# OZ440-SE100-CAR003_sheet4.net
KiCad netlist of a schematic drawn in Altium Designer
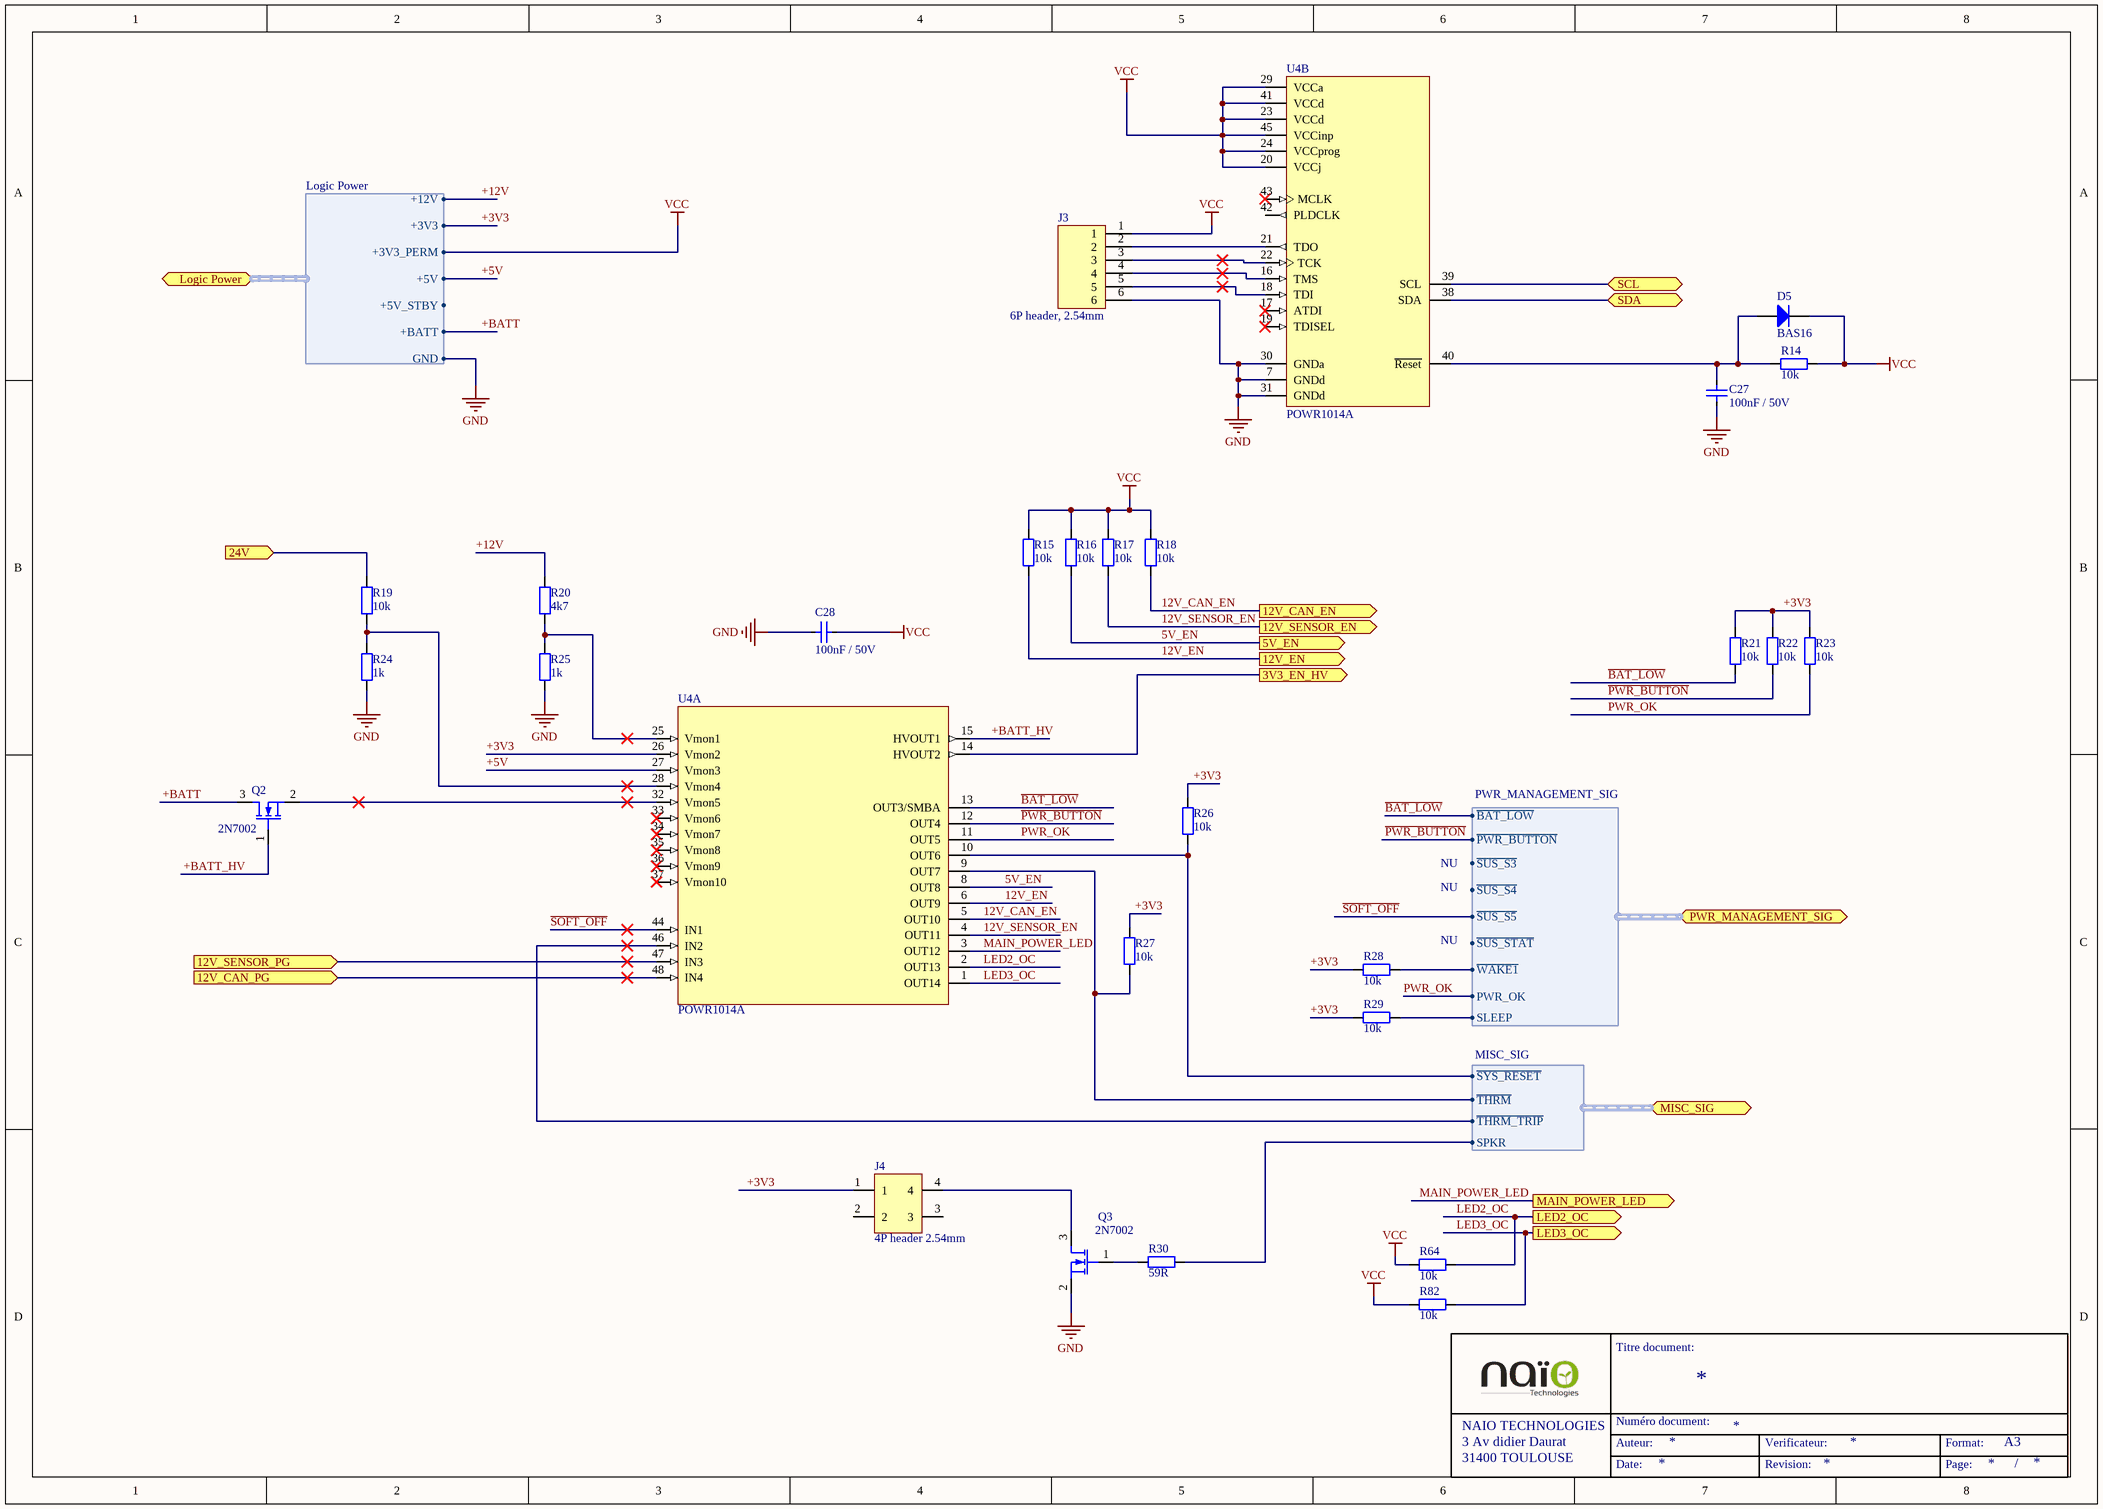
[diagram p0: OZ440-SE100-CAR003_sheet4.SchDoc]

(export (version "E")
  (design (tool "Eeschema 10.0.6"))
  (components
    (comp (ref "C27")
      (value "CAP-SMD")
      (footprint "C0805-STD")
      (description "0805 100nF / 50V  X7R ceramic capacitor")
      (fields
        (field (name "DISPLAYED REFERENCE") "100nF / 50V")
        (field (name "TOLERANCE") "+/- 10%")
        (field (name "MANUFACTURER") "vishay")
      )
      (libsource (lib "lib_NAIO") (part "CAP-SMD"))
    )
    (comp (ref "C28")
      (value "CAP-SMD")
      (footprint "C0805-STD")
      (description "0805 100nF / 50V  X7R ceramic capacitor")
      (fields
        (field (name "DISPLAYED REFERENCE") "100nF / 50V")
        (field (name "TOLERANCE") "+/- 10%")
        (field (name "MANUFACTURER") "vishay")
      )
      (libsource (lib "lib_NAIO") (part "CAP-SMD"))
    )
    (comp (ref "D5")
      (value "BAS16-SOT23")
      (footprint "SOT23-STD")
      (description "100V / 120mA signal  diode")
      (fields (field (name "DISPLAYED REFERENCE") "BAS16") (field (name "MANUFACTURER") "NXP"))
      (libsource (lib "lib_NAIO") (part "BAS16-SOT23"))
    )
    (comp (ref "J3")
      (value "CONN-STD-6P_1ROW")
      (footprint "6P_HEADER-STD_TH_1ROW")
      (description "6P, 1 row, 2.54mm header")
      (fields (field (name "DISPLAYED REFERENCE") "6P header, 2.54mm") (field (name "MANUFACTURER") "FCI"))
      (libsource (lib "lib_NAIO") (part "CONN-STD-6P_1ROW"))
    )
    (comp (ref "J4")
      (value "CONN-STD-4P_2ROW")
      (footprint "4P_HEADER-SPE-1241050-2")
      (description "4P, 2 rows, 2.54mm header")
      (fields
        (field (name "DISPLAYED REFERENCE") "4P header 2.54mm")
        (field (name "MANUFACTURER") "TE CONNECTIVITY")
      )
      (libsource (lib "lib_NAIO") (part "CONN-STD-4P_2ROW"))
    )
    (comp (ref "Q2")
      (value "2N7002-SMD3P")
      (footprint "SOT23-SPE-2N7002")
      (description "N-Channel Enhancement Mode Field Effect Transistor")
      (fields (field (name "DISPLAYED REFERENCE") "2N7002") (field (name "MANUFACTURER") "FAIRCHILD"))
      (libsource (lib "lib_NAIO") (part "2N7002-SMD3P"))
    )
    (comp (ref "Q3")
      (value "2N7002-SMD3P")
      (footprint "SOT23-SPE-2N7002")
      (description "N-Channel Enhancement Mode Field Effect Transistor")
      (fields (field (name "DISPLAYED REFERENCE") "2N7002") (field (name "MANUFACTURER") "FAIRCHILD"))
      (libsource (lib "lib_NAIO") (part "2N7002-SMD3P"))
    )
    (comp (ref "R14")
      (value "RES-SMD")
      (footprint "R0805-STD")
      (description "10k Ohm 0805 SMD resistor")
      (fields
        (field (name "DISPLAYED REFERENCE") "10k")
        (field (name "TOLERANCE") "1 %")
        (field (name "MANUFACTURER") "Vishay")
      )
      (libsource (lib "") (part "RES-SMD_2"))
    )
    (comp (ref "R15")
      (value "RES-SMD")
      (footprint "R0805-STD")
      (description "10k Ohm 0805 SMD resistor")
      (fields
        (field (name "DISPLAYED REFERENCE") "10k")
        (field (name "TOLERANCE") "1 %")
        (field (name "MANUFACTURER") "Vishay")
      )
      (libsource (lib "") (part "RES-SMD_1"))
    )
    (comp (ref "R16")
      (value "RES-SMD")
      (footprint "R0805-STD")
      (description "10k Ohm 0805 SMD resistor")
      (fields
        (field (name "DISPLAYED REFERENCE") "10k")
        (field (name "TOLERANCE") "1 %")
        (field (name "MANUFACTURER") "Vishay")
      )
      (libsource (lib "") (part "RES-SMD_1"))
    )
    (comp (ref "R17")
      (value "RES-SMD")
      (footprint "R0805-STD")
      (description "10k Ohm 0805 SMD resistor")
      (fields
        (field (name "DISPLAYED REFERENCE") "10k")
        (field (name "TOLERANCE") "1 %")
        (field (name "MANUFACTURER") "Vishay")
      )
      (libsource (lib "") (part "RES-SMD_1"))
    )
    (comp (ref "R18")
      (value "RES-SMD")
      (footprint "R0805-STD")
      (description "10k Ohm 0805 SMD resistor")
      (fields
        (field (name "DISPLAYED REFERENCE") "10k")
        (field (name "TOLERANCE") "1 %")
        (field (name "MANUFACTURER") "Vishay")
      )
      (libsource (lib "") (part "RES-SMD_1"))
    )
    (comp (ref "R19")
      (value "RES-SMD")
      (footprint "R0805-STD")
      (description "10k Ohm 0805 SMD resistor")
      (fields
        (field (name "DISPLAYED REFERENCE") "10k")
        (field (name "TOLERANCE") "1 %")
        (field (name "MANUFACTURER") "Vishay")
      )
      (libsource (lib "lib_NAIO") (part "RES-SMD"))
    )
    (comp (ref "R20")
      (value "RES-SMD")
      (footprint "R0805-STD")
      (description "4,7k Ohm 0805 SMD resistor")
      (fields
        (field (name "DISPLAYED REFERENCE") "4k7")
        (field (name "TOLERANCE") "1 %")
        (field (name "MANUFACTURER") "Vishay")
      )
      (libsource (lib "lib_NAIO") (part "RES-SMD"))
    )
    (comp (ref "R21")
      (value "RES-SMD")
      (footprint "R0805-STD")
      (description "10k Ohm 0805 SMD resistor")
      (fields
        (field (name "DISPLAYED REFERENCE") "10k")
        (field (name "TOLERANCE") "1 %")
        (field (name "MANUFACTURER") "Vishay")
      )
      (libsource (lib "") (part "RES-SMD_1"))
    )
    (comp (ref "R22")
      (value "RES-SMD")
      (footprint "R0805-STD")
      (description "10k Ohm 0805 SMD resistor")
      (fields
        (field (name "DISPLAYED REFERENCE") "10k")
        (field (name "TOLERANCE") "1 %")
        (field (name "MANUFACTURER") "Vishay")
      )
      (libsource (lib "") (part "RES-SMD_1"))
    )
    (comp (ref "R23")
      (value "RES-SMD")
      (footprint "R0805-STD")
      (description "10k Ohm 0805 SMD resistor")
      (fields
        (field (name "DISPLAYED REFERENCE") "10k")
        (field (name "TOLERANCE") "1 %")
        (field (name "MANUFACTURER") "Vishay")
      )
      (libsource (lib "") (part "RES-SMD_1"))
    )
    (comp (ref "R24")
      (value "RES-SMD")
      (footprint "R0805-STD")
      (description "1k Ohm 0805 SMD resistor")
      (fields
        (field (name "DISPLAYED REFERENCE") "1k")
        (field (name "TOLERANCE") "1 %")
        (field (name "MANUFACTURER") "Vishay")
      )
      (libsource (lib "lib_NAIO") (part "RES-SMD"))
    )
    (comp (ref "R25")
      (value "RES-SMD")
      (footprint "R0805-STD")
      (description "1k Ohm 0805 SMD resistor")
      (fields
        (field (name "DISPLAYED REFERENCE") "1k")
        (field (name "TOLERANCE") "1 %")
        (field (name "MANUFACTURER") "Vishay")
      )
      (libsource (lib "lib_NAIO") (part "RES-SMD"))
    )
    (comp (ref "R26")
      (value "RES-SMD")
      (footprint "R0805-STD")
      (description "10k Ohm 0805 SMD resistor")
      (fields
        (field (name "DISPLAYED REFERENCE") "10k")
        (field (name "TOLERANCE") "1 %")
        (field (name "MANUFACTURER") "Vishay")
      )
      (libsource (lib "") (part "RES-SMD_1"))
    )
    (comp (ref "R27")
      (value "RES-SMD")
      (footprint "R0805-STD")
      (description "10k Ohm 0805 SMD resistor")
      (fields
        (field (name "DISPLAYED REFERENCE") "10k")
        (field (name "TOLERANCE") "1 %")
        (field (name "MANUFACTURER") "Vishay")
      )
      (libsource (lib "") (part "RES-SMD_1"))
    )
    (comp (ref "R28")
      (value "RES-SMD")
      (footprint "R0805-STD")
      (description "10k Ohm 0805 SMD resistor")
      (fields
        (field (name "DISPLAYED REFERENCE") "10k")
        (field (name "TOLERANCE") "1 %")
        (field (name "MANUFACTURER") "Vishay")
      )
      (libsource (lib "") (part "RES-SMD_2"))
    )
    (comp (ref "R29")
      (value "RES-SMD")
      (footprint "R0805-STD")
      (description "10k Ohm 0805 SMD resistor")
      (fields
        (field (name "DISPLAYED REFERENCE") "10k")
        (field (name "TOLERANCE") "1 %")
        (field (name "MANUFACTURER") "Vishay")
      )
      (libsource (lib "") (part "RES-SMD_2"))
    )
    (comp (ref "R30")
      (value "RES-SMD")
      (footprint "R0805-STD")
      (description "59 Ohm 0805 SMD resistor")
      (fields
        (field (name "DISPLAYED REFERENCE") "59R")
        (field (name "TOLERANCE") "1 %")
        (field (name "MANUFACTURER") "Vishay")
      )
      (libsource (lib "") (part "RES-SMD_3"))
    )
    (comp (ref "R64")
      (value "RES-SMD")
      (footprint "R0805-STD")
      (description "10k Ohm 0805 SMD resistor")
      (fields
        (field (name "DISPLAYED REFERENCE") "10k")
        (field (name "TOLERANCE") "1 %")
        (field (name "MANUFACTURER") "Vishay")
      )
      (libsource (lib "") (part "RES-SMD_2"))
    )
    (comp (ref "R82")
      (value "RES-SMD")
      (footprint "R0805-STD")
      (description "10k Ohm 0805 SMD resistor")
      (fields
        (field (name "DISPLAYED REFERENCE") "10k")
        (field (name "TOLERANCE") "1 %")
        (field (name "MANUFACTURER") "Vishay")
      )
      (libsource (lib "") (part "RES-SMD_2"))
    )
    (comp (ref "U4")
      (value "PWR1014A-TQFP48")
      (footprint "TQFP48-SPE-PWR1014")
      (description "ispPAC power manager")
      (fields (field (name "DISPLAYED REFERENCE") "POWR1014A") (field (name "MANUFACTURER") "LATTICE"))
      (libsource (lib "lib_NAIO") (part "PWR1014A-TQFP48"))
    )
  )
  (nets
    (net (code "5") (name "/+3V3") (class "Default")
      (node (ref "J4") (pin "1") (pinfunction "1_1") (pintype "passive"))
      (node (ref "R21") (pin "1") (pinfunction "1_1") (pintype "passive"))
      (node (ref "R22") (pin "1") (pinfunction "1_1") (pintype "passive"))
      (node (ref "R23") (pin "1") (pinfunction "1_1") (pintype "passive"))
      (node (ref "R26") (pin "1") (pinfunction "1_1") (pintype "passive"))
      (node (ref "R27") (pin "1") (pinfunction "1_1") (pintype "passive"))
      (node (ref "R28") (pin "2") (pinfunction "2_2") (pintype "passive"))
      (node (ref "R29") (pin "2") (pinfunction "2_2") (pintype "passive"))
      (node (ref "U4") (pin "26") (pinfunction "Vmon2_26") (pintype "input"))
    )
    (net (code "6") (name "/+5V") (class "Default")
      (node (ref "U4") (pin "27") (pinfunction "Vmon3_27") (pintype "input"))
    )
    (net (code "7") (name "/+12V") (class "Default")
      (node (ref "R20") (pin "2") (pinfunction "2_2") (pintype "passive"))
    )
    (net (code "8") (name "/+BATT") (class "Default")
      (node (ref "Q2") (pin "3") (pinfunction "D_3") (pintype "passive"))
    )
    (net (code "9") (name "/+BATT_HV") (class "Default")
      (node (ref "Q2") (pin "1") (pinfunction "G_1") (pintype "passive"))
      (node (ref "U4") (pin "15") (pinfunction "HVOUT1_15") (pintype "output"))
    )
    (net (code "10") (name "/3V3_EN_HV") (class "Default")
      (node (ref "U4") (pin "14") (pinfunction "HVOUT2_14") (pintype "output"))
    )
    (net (code "11") (name "/5V_EN") (class "Default")
      (node (ref "R16") (pin "2") (pinfunction "2_2") (pintype "passive"))
      (node (ref "U4") (pin "8") (pinfunction "OUT8_8") (pintype "open_collector"))
    )
    (net (code "12") (name "/12V_CAN_EN") (class "Default")
      (node (ref "R18") (pin "2") (pinfunction "2_2") (pintype "passive"))
      (node (ref "U4") (pin "5") (pinfunction "OUT10_5") (pintype "open_collector"))
    )
    (net (code "13") (name "/12V_CAN_PG") (class "Default")
      (node (ref "U4") (pin "48") (pinfunction "IN4_48") (pintype "input"))
    )
    (net (code "14") (name "/12V_EN") (class "Default")
      (node (ref "R15") (pin "2") (pinfunction "2_2") (pintype "passive"))
      (node (ref "U4") (pin "6") (pinfunction "OUT9_6") (pintype "open_collector"))
    )
    (net (code "15") (name "/12V_SENSOR_EN") (class "Default")
      (node (ref "R17") (pin "2") (pinfunction "2_2") (pintype "passive"))
      (node (ref "U4") (pin "4") (pinfunction "OUT11_4") (pintype "open_collector"))
    )
    (net (code "16") (name "/12V_SENSOR_PG") (class "Default")
      (node (ref "U4") (pin "47") (pinfunction "IN3_47") (pintype "input"))
    )
    (net (code "17") (name "/24V") (class "Default")
      (node (ref "R19") (pin "2") (pinfunction "2_2") (pintype "passive"))
    )
    (net (code "18") (name "/BAT_LOW") (class "Default")
      (node (ref "R21") (pin "2") (pinfunction "2_2") (pintype "passive"))
      (node (ref "U4") (pin "13") (pinfunction "OUT3/SMBA_13") (pintype "open_collector"))
    )
    (net (code "19") (name "/LED2_OC") (class "Default")
      (node (ref "R64") (pin "1") (pinfunction "1_1") (pintype "passive"))
      (node (ref "U4") (pin "2") (pinfunction "OUT13_2") (pintype "open_collector"))
    )
    (net (code "20") (name "/LED3_OC") (class "Default")
      (node (ref "R82") (pin "1") (pinfunction "1_1") (pintype "passive"))
      (node (ref "U4") (pin "1") (pinfunction "OUT14_1") (pintype "open_collector"))
    )
    (net (code "21") (name "/MAIN_POWER_LED") (class "Default")
      (node (ref "U4") (pin "3") (pinfunction "OUT12_3") (pintype "open_collector"))
    )
    (net (code "22") (name "/PWR_BUTTON") (class "Default")
      (node (ref "R22") (pin "2") (pinfunction "2_2") (pintype "passive"))
      (node (ref "U4") (pin "12") (pinfunction "OUT4_12") (pintype "open_collector"))
    )
    (net (code "23") (name "/PWR_OK") (class "Default")
      (node (ref "R23") (pin "2") (pinfunction "2_2") (pintype "passive"))
      (node (ref "U4") (pin "11") (pinfunction "OUT5_11") (pintype "open_collector"))
    )
    (net (code "24") (name "/SCL") (class "Default")
      (node (ref "U4") (pin "39") (pinfunction "SCL_39") (pintype "passive"))
    )
    (net (code "25") (name "/SDA") (class "Default")
      (node (ref "U4") (pin "38") (pinfunction "SDA_38") (pintype "passive"))
    )
    (net (code "26") (name "/SLEEP") (class "Default")
      (node (ref "R29") (pin "1") (pinfunction "1_1") (pintype "passive"))
    )
    (net (code "27") (name "/SOFT_OFF") (class "Default")
      (node (ref "U4") (pin "44") (pinfunction "IN1_44") (pintype "input"))
    )
    (net (code "28") (name "/SPKR") (class "Default")
      (node (ref "R30") (pin "2") (pinfunction "2_2") (pintype "passive"))
    )
    (net (code "32") (name "/~{SYS_RESET}") (class "Default")
      (node (ref "R26") (pin "2") (pinfunction "2_2") (pintype "passive"))
      (node (ref "U4") (pin "10") (pinfunction "OUT6_10") (pintype "open_collector"))
    )
    (net (code "33") (name "/~{THRM_TRIP}") (class "Default")
      (node (ref "U4") (pin "46") (pinfunction "IN2_46") (pintype "input"))
    )
    (net (code "34") (name "/~{THRM}") (class "Default")
      (node (ref "R27") (pin "2") (pinfunction "2_2") (pintype "passive"))
      (node (ref "U4") (pin "9") (pinfunction "OUT7_9") (pintype "open_collector"))
    )
    (net (code "35") (name "/~{WAKE1}") (class "Default")
      (node (ref "R28") (pin "1") (pinfunction "1_1") (pintype "passive"))
    )
    (net (code "36") (name "GND") (class "Default")
      (node (ref "C27") (pin "1") (pinfunction "1_1") (pintype "passive"))
      (node (ref "C28") (pin "1") (pinfunction "1_1") (pintype "passive"))
      (node (ref "J3") (pin "6") (pinfunction "6_6") (pintype "passive"))
      (node (ref "Q3") (pin "2") (pinfunction "S_2") (pintype "passive"))
      (node (ref "R24") (pin "1") (pinfunction "1_1") (pintype "passive"))
      (node (ref "R25") (pin "1") (pinfunction "1_1") (pintype "passive"))
      (node (ref "U4") (pin "30") (pinfunction "GNDa_30") (pintype "power_in"))
      (node (ref "U4") (pin "31") (pinfunction "GNDd_31") (pintype "power_in"))
      (node (ref "U4") (pin "7") (pinfunction "GNDd_7") (pintype "power_in"))
    )
    (net (code "37") (name "Net-(D5-A)") (class "Default")
      (node (ref "C27") (pin "2") (pinfunction "2_2") (pintype "passive"))
      (node (ref "D5") (pin "1") (pinfunction "A_1") (pintype "passive"))
      (node (ref "R14") (pin "2") (pinfunction "2_2") (pintype "passive"))
      (node (ref "U4") (pin "40") (pinfunction "Reset_40") (pintype "passive"))
    )
    (net (code "38") (name "Net-(Q2-S)") (class "Default")
      (node (ref "Q2") (pin "2") (pinfunction "S_2") (pintype "passive"))
      (node (ref "U4") (pin "32") (pinfunction "Vmon5_32") (pintype "input"))
    )
    (net (code "39") (name "Net-(Q3-D)") (class "Default")
      (node (ref "J4") (pin "4") (pinfunction "4_4") (pintype "passive"))
      (node (ref "Q3") (pin "3") (pinfunction "D_3") (pintype "passive"))
    )
    (net (code "40") (name "Net-(Q3-G)") (class "Default")
      (node (ref "Q3") (pin "1") (pinfunction "G_1") (pintype "passive"))
      (node (ref "R30") (pin "1") (pinfunction "1_1") (pintype "passive"))
    )
    (net (code "41") (name "Net-(U4A-Vmon1)") (class "Default")
      (node (ref "R20") (pin "1") (pinfunction "1_1") (pintype "passive"))
      (node (ref "R25") (pin "2") (pinfunction "2_2") (pintype "passive"))
      (node (ref "U4") (pin "25") (pinfunction "Vmon1_25") (pintype "input"))
    )
    (net (code "42") (name "Net-(U4A-Vmon4)") (class "Default")
      (node (ref "R19") (pin "1") (pinfunction "1_1") (pintype "passive"))
      (node (ref "R24") (pin "2") (pinfunction "2_2") (pintype "passive"))
      (node (ref "U4") (pin "28") (pinfunction "Vmon4_28") (pintype "input"))
    )
    (net (code "43") (name "Net-(U4B-TCK)") (class "Default")
      (node (ref "J3") (pin "3") (pinfunction "3_3") (pintype "passive"))
      (node (ref "U4") (pin "22") (pinfunction "TCK_22") (pintype "input"))
    )
    (net (code "44") (name "Net-(U4B-TDI)") (class "Default")
      (node (ref "J3") (pin "5") (pinfunction "5_5") (pintype "passive"))
      (node (ref "U4") (pin "18") (pinfunction "TDI_18") (pintype "input"))
    )
    (net (code "45") (name "Net-(U4B-TDO)") (class "Default")
      (node (ref "J3") (pin "2") (pinfunction "2_2") (pintype "passive"))
      (node (ref "U4") (pin "21") (pinfunction "TDO_21") (pintype "output"))
    )
    (net (code "46") (name "Net-(U4B-TMS)") (class "Default")
      (node (ref "J3") (pin "4") (pinfunction "4_4") (pintype "passive"))
      (node (ref "U4") (pin "16") (pinfunction "TMS_16") (pintype "input"))
    )
    (net (code "47") (name "VCC") (class "Default")
      (node (ref "C28") (pin "2") (pinfunction "2_2") (pintype "passive"))
      (node (ref "D5") (pin "3") (pinfunction "K_3") (pintype "passive"))
      (node (ref "J3") (pin "1") (pinfunction "1_1") (pintype "passive"))
      (node (ref "R14") (pin "1") (pinfunction "1_1") (pintype "passive"))
      (node (ref "R15") (pin "1") (pinfunction "1_1") (pintype "passive"))
      (node (ref "R16") (pin "1") (pinfunction "1_1") (pintype "passive"))
      (node (ref "R17") (pin "1") (pinfunction "1_1") (pintype "passive"))
      (node (ref "R18") (pin "1") (pinfunction "1_1") (pintype "passive"))
      (node (ref "R64") (pin "2") (pinfunction "2_2") (pintype "passive"))
      (node (ref "R82") (pin "2") (pinfunction "2_2") (pintype "passive"))
      (node (ref "U4") (pin "20") (pinfunction "VCCj_20") (pintype "power_in"))
      (node (ref "U4") (pin "23") (pinfunction "VCCd_23") (pintype "power_in"))
      (node (ref "U4") (pin "24") (pinfunction "VCCprog_24") (pintype "power_in"))
      (node (ref "U4") (pin "29") (pinfunction "VCCa_29") (pintype "power_in"))
      (node (ref "U4") (pin "41") (pinfunction "VCCd_41") (pintype "power_in"))
      (node (ref "U4") (pin "45") (pinfunction "VCCinp_45") (pintype "power_in"))
    )
    (net (code "48") (name "unconnected-(J4-Pad2)") (class "Default")
      (node (ref "J4") (pin "2") (pinfunction "2_2") (pintype "passive"))
    )
    (net (code "49") (name "unconnected-(J4-Pad3)") (class "Default")
      (node (ref "J4") (pin "3") (pinfunction "3_3") (pintype "passive"))
    )
    (net (code "50") (name "unconnected-(U4A-Vmon6-Pad33)") (class "Default")
      (node (ref "U4") (pin "33") (pinfunction "Vmon6_33") (pintype "input+no_connect"))
    )
    (net (code "51") (name "unconnected-(U4A-Vmon7-Pad34)") (class "Default")
      (node (ref "U4") (pin "34") (pinfunction "Vmon7_34") (pintype "input+no_connect"))
    )
    (net (code "52") (name "unconnected-(U4A-Vmon8-Pad35)") (class "Default")
      (node (ref "U4") (pin "35") (pinfunction "Vmon8_35") (pintype "input+no_connect"))
    )
    (net (code "53") (name "unconnected-(U4A-Vmon9-Pad36)") (class "Default")
      (node (ref "U4") (pin "36") (pinfunction "Vmon9_36") (pintype "input+no_connect"))
    )
    (net (code "54") (name "unconnected-(U4A-Vmon10-Pad37)") (class "Default")
      (node (ref "U4") (pin "37") (pinfunction "Vmon10_37") (pintype "input+no_connect"))
    )
    (net (code "55") (name "unconnected-(U4B-ATDI-Pad17)") (class "Default")
      (node (ref "U4") (pin "17") (pinfunction "ATDI_17") (pintype "input+no_connect"))
    )
    (net (code "56") (name "unconnected-(U4B-MCLK-Pad43)") (class "Default")
      (node (ref "U4") (pin "43") (pinfunction "MCLK_43") (pintype "input+no_connect"))
    )
    (net (code "57") (name "unconnected-(U4B-PLDCLK-Pad42)") (class "Default")
      (node (ref "U4") (pin "42") (pinfunction "PLDCLK_42") (pintype "output"))
    )
    (net (code "58") (name "unconnected-(U4B-TDISEL-Pad19)") (class "Default")
      (node (ref "U4") (pin "19") (pinfunction "TDISEL_19") (pintype "input+no_connect"))
    )
  )
)
